# final.net
KiCad netlist of a schematic drawn in EAGLE
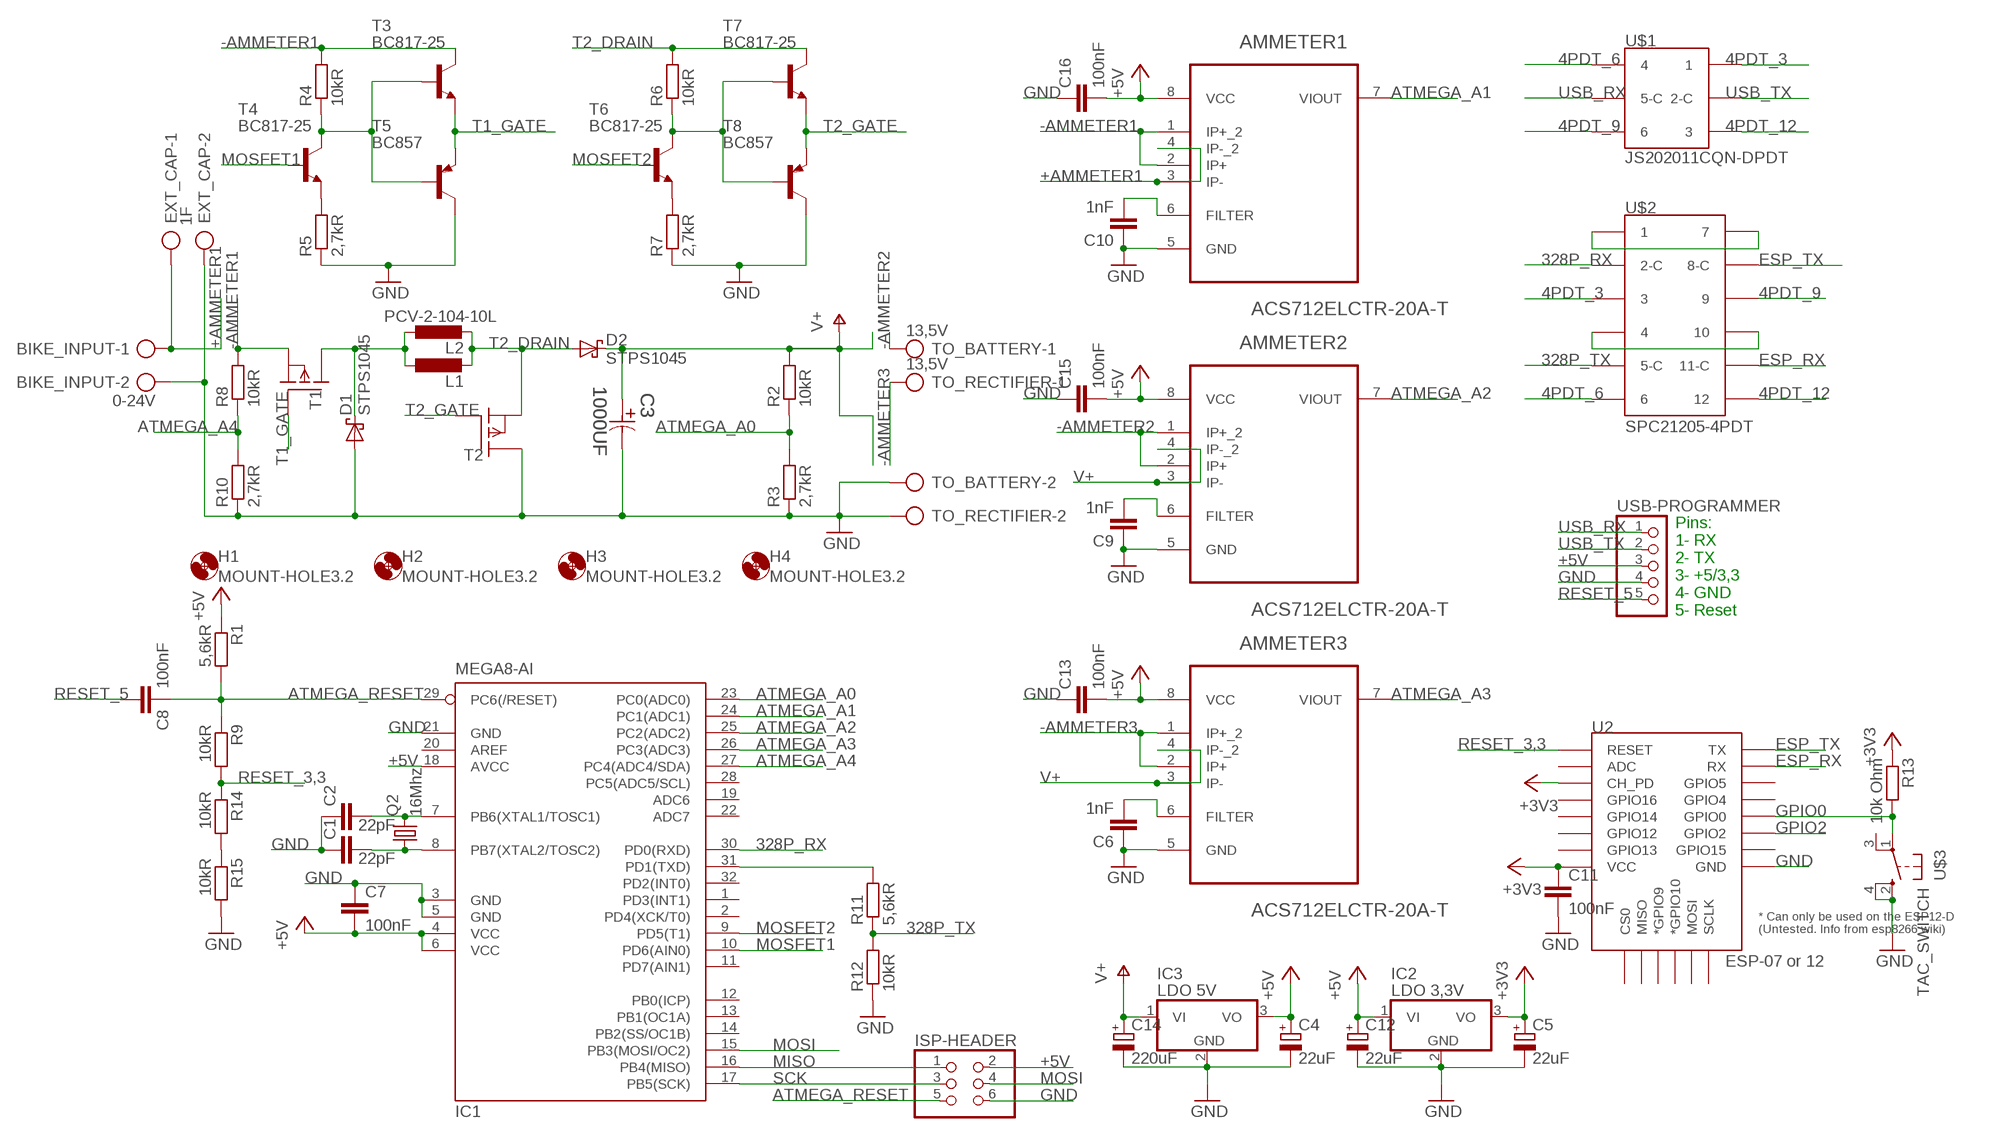
[diagram p0: schematic, sheet 1]

(export (version "E")
  (design (tool "Eeschema 10.0.6"))
  (components
    (comp (ref "AMMETER1")
      (value "ACS712ELCTR-20A-T")
      (footprint "eagle-import:SOIC127P600X175-8N")
      (libsource (lib "eagle-import") (part "ACS712ELCTR-20A-T"))
    )
    (comp (ref "AMMETER2")
      (value "ACS712ELCTR-20A-T")
      (footprint "eagle-import:SOIC127P600X175-8N")
      (libsource (lib "eagle-import") (part "ACS712ELCTR-20A-T"))
    )
    (comp (ref "AMMETER3")
      (value "ACS712ELCTR-20A-T")
      (footprint "eagle-import:SOIC127P600X175-8N")
      (libsource (lib "eagle-import") (part "ACS712ELCTR-20A-T"))
    )
    (comp (ref "BIKE_INPUT")
      (value "0-24V")
      (footprint "eagle-import:AK500_2")
      (libsource (lib "eagle-import") (part "AK500/2"))
    )
    (comp (ref "C1")
      (value "22pF")
      (footprint "eagle-import:C0805")
      (libsource (lib "eagle-import") (part "C-EUC0805"))
    )
    (comp (ref "C2")
      (value "22pF")
      (footprint "eagle-import:C0805")
      (libsource (lib "eagle-import") (part "C-EUC0805"))
    )
    (comp (ref "C3")
      (value "1000UF")
      (footprint "eagle-import:CAPAE1700X1700N")
      (fields (field (name "MPN") "EEVFK1H102M") (field (name "TOLERANCE") "±20 %"))
      (libsource (lib "eagle-import") (part "EEV--CASE-J16FK1H102M"))
    )
    (comp (ref "C4")
      (value "22uF")
      (footprint "eagle-import:153CLV-0505")
      (libsource (lib "eagle-import") (part "CPOL-EU153CLV-0505"))
    )
    (comp (ref "C5")
      (value "22uF")
      (footprint "eagle-import:153CLV-0505")
      (libsource (lib "eagle-import") (part "CPOL-EU153CLV-0505"))
    )
    (comp (ref "C6")
      (value "1nF")
      (footprint "eagle-import:C0805")
      (libsource (lib "eagle-import") (part "C-EUC0805"))
    )
    (comp (ref "C7")
      (value "100nF")
      (footprint "eagle-import:C0805")
      (libsource (lib "eagle-import") (part "C-EUC0805"))
    )
    (comp (ref "C8")
      (value "100nF")
      (footprint "eagle-import:C0805")
      (libsource (lib "eagle-import") (part "C-EUC0805"))
    )
    (comp (ref "C9")
      (value "1nF")
      (footprint "eagle-import:C0805")
      (libsource (lib "eagle-import") (part "C-EUC0805"))
    )
    (comp (ref "C10")
      (value "1nF")
      (footprint "eagle-import:C0805")
      (libsource (lib "eagle-import") (part "C-EUC0805"))
    )
    (comp (ref "C11")
      (value "100nF")
      (footprint "eagle-import:C0805")
      (libsource (lib "eagle-import") (part "C-EUC0805"))
    )
    (comp (ref "C12")
      (value "22uF")
      (footprint "eagle-import:153CLV-0505")
      (libsource (lib "eagle-import") (part "CPOL-EU153CLV-0505"))
    )
    (comp (ref "C13")
      (value "100nF")
      (footprint "eagle-import:C0805")
      (libsource (lib "eagle-import") (part "C-EUC0805"))
    )
    (comp (ref "C14")
      (value "220uF")
      (footprint "eagle-import:153CLV-0807")
      (libsource (lib "eagle-import") (part "CPOL-EU153CLV-0807"))
    )
    (comp (ref "C15")
      (value "100nF")
      (footprint "eagle-import:C0805")
      (libsource (lib "eagle-import") (part "C-EUC0805"))
    )
    (comp (ref "C16")
      (value "100nF")
      (footprint "eagle-import:C0805")
      (libsource (lib "eagle-import") (part "C-EUC0805"))
    )
    (comp (ref "D1")
      (value "STPS1045")
      (footprint "eagle-import:TO220AC")
      (libsource (lib "eagle-import") (part "STPS1045"))
    )
    (comp (ref "D2")
      (value "STPS1045")
      (footprint "eagle-import:TO220AC")
      (libsource (lib "eagle-import") (part "STPS1045"))
    )
    (comp (ref "EXT_CAP")
      (value "1F")
      (footprint "eagle-import:AK500_2")
      (libsource (lib "eagle-import") (part "AK500/2"))
    )
    (comp (ref "H1")
      (value "MOUNT-HOLE3.2")
      (footprint "eagle-import:3,2")
      (libsource (lib "eagle-import") (part "MOUNT-HOLE3.2"))
    )
    (comp (ref "H2")
      (value "MOUNT-HOLE3.2")
      (footprint "eagle-import:3,2")
      (libsource (lib "eagle-import") (part "MOUNT-HOLE3.2"))
    )
    (comp (ref "H3")
      (value "MOUNT-HOLE3.2")
      (footprint "eagle-import:3,2")
      (libsource (lib "eagle-import") (part "MOUNT-HOLE3.2"))
    )
    (comp (ref "H4")
      (value "MOUNT-HOLE3.2")
      (footprint "eagle-import:3,2")
      (libsource (lib "eagle-import") (part "MOUNT-HOLE3.2"))
    )
    (comp (ref "IC1")
      (value "MEGA8-AI")
      (footprint "eagle-import:TQFP32-08")
      (fields (field (name "MPN") "ATMEGA8-16AU"))
      (libsource (lib "eagle-import") (part "MEGA8-AI"))
    )
    (comp (ref "IC2")
      (value "LDO 3,3V")
      (footprint "eagle-import:SOT223")
      (libsource (lib "eagle-import") (part "MCP1703DB"))
    )
    (comp (ref "IC3")
      (value "LDO 5V")
      (footprint "eagle-import:SOT223")
      (libsource (lib "eagle-import") (part "MCP1703DB"))
    )
    (comp (ref "ISP-HEADER")
      (value "PINHD-2X3")
      (footprint "eagle-import:2X03")
      (libsource (lib "eagle-import") (part "PINHD-2X3"))
    )
    (comp (ref "L1")
      (value "PCV-2-104-10L")
      (footprint "eagle-import:TJ5-U2")
      (libsource (lib "eagle-import") (part "PCV-2-104-10L"))
    )
    (comp (ref "L2")
      (value "PCV-2-104-10L")
      (footprint "eagle-import:TJ5-U2")
      (libsource (lib "eagle-import") (part "PCV-2-104-10L"))
    )
    (comp (ref "Q2")
      (value "16Mhz")
      (footprint "eagle-import:HC49UP")
      (libsource (lib "eagle-import") (part "CRYSTALHC49UP"))
    )
    (comp (ref "R1")
      (value "5,6kR")
      (footprint "eagle-import:M0805")
      (libsource (lib "eagle-import") (part "R-EU_M0805"))
    )
    (comp (ref "R2")
      (value "10kR")
      (footprint "eagle-import:M0805")
      (libsource (lib "eagle-import") (part "R-EU_M0805"))
    )
    (comp (ref "R3")
      (value "2,7kR")
      (footprint "eagle-import:M0805")
      (libsource (lib "eagle-import") (part "R-EU_M0805"))
    )
    (comp (ref "R4")
      (value "10kR")
      (footprint "eagle-import:M0805")
      (libsource (lib "eagle-import") (part "R-EU_M0805"))
    )
    (comp (ref "R5")
      (value "2,7kR")
      (footprint "eagle-import:M0805")
      (libsource (lib "eagle-import") (part "R-EU_M0805"))
    )
    (comp (ref "R6")
      (value "10kR")
      (footprint "eagle-import:M0805")
      (libsource (lib "eagle-import") (part "R-EU_M0805"))
    )
    (comp (ref "R7")
      (value "2,7kR")
      (footprint "eagle-import:M0805")
      (libsource (lib "eagle-import") (part "R-EU_M0805"))
    )
    (comp (ref "R8")
      (value "10kR")
      (footprint "eagle-import:M0805")
      (libsource (lib "eagle-import") (part "R-EU_M0805"))
    )
    (comp (ref "R9")
      (value "10kR")
      (footprint "eagle-import:M0805")
      (libsource (lib "eagle-import") (part "R-EU_M0805"))
    )
    (comp (ref "R10")
      (value "2,7kR")
      (footprint "eagle-import:M0805")
      (libsource (lib "eagle-import") (part "R-EU_M0805"))
    )
    (comp (ref "R11")
      (value "5,6kR")
      (footprint "eagle-import:M0805")
      (libsource (lib "eagle-import") (part "R-EU_M0805"))
    )
    (comp (ref "R12")
      (value "10kR")
      (footprint "eagle-import:M0805")
      (libsource (lib "eagle-import") (part "R-EU_M0805"))
    )
    (comp (ref "R13")
      (value "10k Ohm")
      (footprint "eagle-import:M0805")
      (libsource (lib "eagle-import") (part "R-EU_M0805"))
    )
    (comp (ref "R14")
      (value "10kR")
      (footprint "eagle-import:M0805")
      (libsource (lib "eagle-import") (part "R-EU_M0805"))
    )
    (comp (ref "R15")
      (value "10kR")
      (footprint "eagle-import:M0805")
      (libsource (lib "eagle-import") (part "R-EU_M0805"))
    )
    (comp (ref "T1")
      (value "SUP65P06-20")
      (footprint "eagle-import:TO220")
      (libsource (lib "eagle-import") (part "SUP65P06-20"))
    )
    (comp (ref "T2")
      (value "SUP65P06-20")
      (footprint "eagle-import:TO220")
      (libsource (lib "eagle-import") (part "SUP65P06-20"))
    )
    (comp (ref "T3")
      (value "BC817-25")
      (footprint "eagle-import:SOT23-BEC")
      (libsource (lib "eagle-import") (part "-NPN-SOT23-BECBC817-25"))
    )
    (comp (ref "T4")
      (value "BC817-25")
      (footprint "eagle-import:SOT23-BEC")
      (libsource (lib "eagle-import") (part "-NPN-SOT23-BECBC817-25"))
    )
    (comp (ref "T5")
      (value "BC857")
      (footprint "eagle-import:SOT23-BEC")
      (libsource (lib "eagle-import") (part "-PNP-SOT23-BECBC857ALT1"))
    )
    (comp (ref "T6")
      (value "BC817-25")
      (footprint "eagle-import:SOT23-BEC")
      (libsource (lib "eagle-import") (part "-NPN-SOT23-BECBC817-25"))
    )
    (comp (ref "T7")
      (value "BC817-25")
      (footprint "eagle-import:SOT23-BEC")
      (libsource (lib "eagle-import") (part "-NPN-SOT23-BECBC817-25"))
    )
    (comp (ref "T8")
      (value "BC857")
      (footprint "eagle-import:SOT23-BEC")
      (libsource (lib "eagle-import") (part "-PNP-SOT23-BECBC857ALT1"))
    )
    (comp (ref "TO_BATTERY")
      (value "13,5V")
      (footprint "eagle-import:AK500_2")
      (libsource (lib "eagle-import") (part "AK500/2"))
    )
    (comp (ref "TO_RECTIFIER")
      (value "13,5V")
      (footprint "eagle-import:AK500_2")
      (libsource (lib "eagle-import") (part "AK500/2"))
    )
    (comp (ref "U$1")
      (value "JS202011CQN-DPDT")
      (footprint "eagle-import:2X3_SWITCH")
      (libsource (lib "eagle-import") (part "JS202011CQN-DPDT"))
    )
    (comp (ref "U$2")
      (value "SPC21205-4PDT")
      (footprint "eagle-import:2X6_SWITCH")
      (libsource (lib "eagle-import") (part "SPC21205-4PDT"))
    )
    (comp (ref "U$3")
      (value "TAC_SWITCH")
      (footprint "eagle-import:TL1105SP")
      (libsource (lib "eagle-import") (part "TAC_SWITCH"))
    )
    (comp (ref "U2")
      (value "ESP-07 or 12")
      (footprint "eagle-import:ESP12E-SMD")
      (libsource (lib "eagle-import") (part "ESP12ESMD"))
    )
    (comp (ref "USB-PROGRAMMER")
      (value "PINHD-1X5")
      (footprint "eagle-import:1X05")
      (libsource (lib "eagle-import") (part "PINHD-1X5"))
    )
  )
  (nets
    (net (code "1") (name "+3V3") (class "Default")
      (node (ref "C11") (pin "1") (pinfunction "1_1") (pintype "passive"))
      (node (ref "C5") (pin "+") (pinfunction "+_+") (pintype "passive"))
      (node (ref "IC2") (pin "3") (pinfunction "VO_3") (pintype "passive"))
      (node (ref "R13") (pin "1") (pinfunction "1_1") (pintype "passive"))
      (node (ref "U2") (pin "CH_PD") (pinfunction "CH_PD_CH_PD") (pintype "bidirectional"))
      (node (ref "U2") (pin "VCC") (pinfunction "VCC_VCC") (pintype "bidirectional"))
    )
    (net (code "2") (name "+5V") (class "Default")
      (node (ref "AMMETER1") (pin "8") (pinfunction "VCC_8") (pintype "power_in"))
      (node (ref "AMMETER2") (pin "8") (pinfunction "VCC_8") (pintype "power_in"))
      (node (ref "AMMETER3") (pin "8") (pinfunction "VCC_8") (pintype "power_in"))
      (node (ref "C12") (pin "+") (pinfunction "+_+") (pintype "passive"))
      (node (ref "C13") (pin "2") (pinfunction "2_2") (pintype "passive"))
      (node (ref "C15") (pin "2") (pinfunction "2_2") (pintype "passive"))
      (node (ref "C16") (pin "2") (pinfunction "2_2") (pintype "passive"))
      (node (ref "C4") (pin "+") (pinfunction "+_+") (pintype "passive"))
      (node (ref "C7") (pin "2") (pinfunction "2_2") (pintype "passive"))
      (node (ref "IC1") (pin "18") (pinfunction "AVCC_18") (pintype "power_in"))
      (node (ref "IC1") (pin "4") (pinfunction "VCC_4") (pintype "power_in"))
      (node (ref "IC1") (pin "6") (pinfunction "VCC_6") (pintype "power_in"))
      (node (ref "IC2") (pin "1") (pinfunction "VI_1") (pintype "input"))
      (node (ref "IC3") (pin "3") (pinfunction "VO_3") (pintype "passive"))
      (node (ref "ISP-HEADER") (pin "2") (pinfunction "2_2") (pintype "passive"))
      (node (ref "R1") (pin "1") (pinfunction "1_1") (pintype "passive"))
      (node (ref "USB-PROGRAMMER") (pin "3") (pinfunction "3_3") (pintype "passive"))
    )
    (net (code "3") (name "/+AMMETER1") (class "Default")
      (node (ref "AMMETER1") (pin "3") (pinfunction "IP-_3") (pintype "input"))
      (node (ref "AMMETER1") (pin "4") (pinfunction "IP-_2_4") (pintype "input"))
      (node (ref "BIKE_INPUT") (pin "1") (pinfunction "KL_1") (pintype "passive"))
      (node (ref "EXT_CAP") (pin "1") (pinfunction "KL_1") (pintype "passive"))
    )
    (net (code "4") (name "/-AMMETER1") (class "Default")
      (node (ref "AMMETER1") (pin "1") (pinfunction "IP+_2_1") (pintype "input"))
      (node (ref "AMMETER1") (pin "2") (pinfunction "IP+_2") (pintype "input"))
      (node (ref "R4") (pin "2") (pinfunction "2_2") (pintype "passive"))
      (node (ref "R8") (pin "2") (pinfunction "2_2") (pintype "passive"))
      (node (ref "T1") (pin "3") (pinfunction "S_3") (pintype "passive"))
      (node (ref "T3") (pin "C") (pinfunction "C_C") (pintype "passive"))
    )
    (net (code "5") (name "/-AMMETER2") (class "Default")
      (node (ref "AMMETER2") (pin "1") (pinfunction "IP+_2_1") (pintype "input"))
      (node (ref "AMMETER2") (pin "2") (pinfunction "IP+_2") (pintype "input"))
      (node (ref "TO_BATTERY") (pin "1") (pinfunction "KL_1") (pintype "passive"))
    )
    (net (code "6") (name "/-AMMETER3") (class "Default")
      (node (ref "AMMETER3") (pin "1") (pinfunction "IP+_2_1") (pintype "input"))
      (node (ref "AMMETER3") (pin "2") (pinfunction "IP+_2") (pintype "input"))
      (node (ref "TO_RECTIFIER") (pin "1") (pinfunction "KL_1") (pintype "passive"))
    )
    (net (code "7") (name "/4PDT_3") (class "Default")
      (node (ref "U$1") (pin "1") (pinfunction "1_1") (pintype "bidirectional"))
      (node (ref "U$2") (pin "3") (pinfunction "3_3") (pintype "bidirectional"))
    )
    (net (code "8") (name "/4PDT_6") (class "Default")
      (node (ref "U$1") (pin "4") (pinfunction "4_4") (pintype "bidirectional"))
      (node (ref "U$2") (pin "6") (pinfunction "6_6") (pintype "bidirectional"))
    )
    (net (code "9") (name "/4PDT_9") (class "Default")
      (node (ref "U$1") (pin "6") (pinfunction "6_6") (pintype "bidirectional"))
      (node (ref "U$2") (pin "9") (pinfunction "9_9") (pintype "bidirectional"))
    )
    (net (code "10") (name "/4PDT_12") (class "Default")
      (node (ref "U$1") (pin "3") (pinfunction "3_3") (pintype "bidirectional"))
      (node (ref "U$2") (pin "12") (pinfunction "12_12") (pintype "bidirectional"))
    )
    (net (code "11") (name "/328P_RX") (class "Default")
      (node (ref "IC1") (pin "30") (pinfunction "PD0(RXD)_30") (pintype "bidirectional"))
      (node (ref "U$2") (pin "2-C") (pinfunction "2-C_2-C") (pintype "bidirectional"))
    )
    (net (code "12") (name "/328P_TX") (class "Default")
      (node (ref "R11") (pin "1") (pinfunction "1_1") (pintype "passive"))
      (node (ref "R12") (pin "2") (pinfunction "2_2") (pintype "passive"))
      (node (ref "U$2") (pin "5-C") (pinfunction "5-C_5-C") (pintype "bidirectional"))
    )
    (net (code "13") (name "/ATMEGA_A0") (class "Default")
      (node (ref "IC1") (pin "23") (pinfunction "PC0(ADC0)_23") (pintype "bidirectional"))
      (node (ref "R2") (pin "1") (pinfunction "1_1") (pintype "passive"))
      (node (ref "R3") (pin "2") (pinfunction "2_2") (pintype "passive"))
    )
    (net (code "14") (name "/ATMEGA_A1") (class "Default")
      (node (ref "AMMETER1") (pin "7") (pinfunction "VIOUT_7") (pintype "output"))
      (node (ref "IC1") (pin "24") (pinfunction "PC1(ADC1)_24") (pintype "bidirectional"))
    )
    (net (code "15") (name "/ATMEGA_A2") (class "Default")
      (node (ref "AMMETER2") (pin "7") (pinfunction "VIOUT_7") (pintype "output"))
      (node (ref "IC1") (pin "25") (pinfunction "PC2(ADC2)_25") (pintype "bidirectional"))
    )
    (net (code "16") (name "/ATMEGA_A3") (class "Default")
      (node (ref "AMMETER3") (pin "7") (pinfunction "VIOUT_7") (pintype "output"))
      (node (ref "IC1") (pin "26") (pinfunction "PC3(ADC3)_26") (pintype "bidirectional"))
    )
    (net (code "17") (name "/ATMEGA_A4") (class "Default")
      (node (ref "IC1") (pin "27") (pinfunction "PC4(ADC4/SDA)_27") (pintype "bidirectional"))
      (node (ref "R10") (pin "2") (pinfunction "2_2") (pintype "passive"))
      (node (ref "R8") (pin "1") (pinfunction "1_1") (pintype "passive"))
    )
    (net (code "18") (name "/ATMEGA_RESET") (class "Default")
      (node (ref "C8") (pin "1") (pinfunction "1_1") (pintype "passive"))
      (node (ref "IC1") (pin "29") (pinfunction "PC6(/RESET)_29") (pintype "bidirectional"))
      (node (ref "ISP-HEADER") (pin "5") (pinfunction "5_5") (pintype "passive"))
      (node (ref "R1") (pin "2") (pinfunction "2_2") (pintype "passive"))
      (node (ref "R9") (pin "1") (pinfunction "1_1") (pintype "passive"))
    )
    (net (code "19") (name "/ESP_RX") (class "Default")
      (node (ref "U$2") (pin "11-C") (pinfunction "11-C_11-C") (pintype "bidirectional"))
      (node (ref "U2") (pin "RXD0") (pinfunction "RX_RXD0") (pintype "bidirectional"))
    )
    (net (code "20") (name "/ESP_TX") (class "Default")
      (node (ref "U$2") (pin "8-C") (pinfunction "8-C_8-C") (pintype "bidirectional"))
      (node (ref "U2") (pin "TXD0") (pinfunction "TX_TXD0") (pintype "bidirectional"))
    )
    (net (code "21") (name "/GPIO0") (class "Default")
      (node (ref "R13") (pin "2") (pinfunction "2_2") (pintype "passive"))
      (node (ref "U$3") (pin "1") (pinfunction "P_1") (pintype "passive"))
      (node (ref "U2") (pin "GPIO0") (pinfunction "GPIO0_GPIO0") (pintype "bidirectional"))
    )
    (net (code "22") (name "/GPIO2") (class "Default")
      (node (ref "U2") (pin "GPIO2") (pinfunction "GPIO2_GPIO2") (pintype "bidirectional"))
    )
    (net (code "23") (name "/MISO") (class "Default")
      (node (ref "IC1") (pin "16") (pinfunction "PB4(MISO)_16") (pintype "bidirectional"))
      (node (ref "ISP-HEADER") (pin "1") (pinfunction "1_1") (pintype "passive"))
    )
    (net (code "24") (name "/MOSFET1") (class "Default")
      (node (ref "IC1") (pin "10") (pinfunction "PD6(AIN0)_10") (pintype "bidirectional"))
      (node (ref "T4") (pin "B") (pinfunction "B_B") (pintype "passive"))
    )
    (net (code "25") (name "/MOSFET2") (class "Default")
      (node (ref "IC1") (pin "9") (pinfunction "PD5(T1)_9") (pintype "bidirectional"))
      (node (ref "T6") (pin "B") (pinfunction "B_B") (pintype "passive"))
    )
    (net (code "26") (name "/MOSI") (class "Default")
      (node (ref "IC1") (pin "15") (pinfunction "PB3(MOSI/OC2)_15") (pintype "bidirectional"))
      (node (ref "ISP-HEADER") (pin "4") (pinfunction "4_4") (pintype "passive"))
    )
    (net (code "27") (name "/RESET_3,3") (class "Default")
      (node (ref "R14") (pin "1") (pinfunction "1_1") (pintype "passive"))
      (node (ref "R9") (pin "2") (pinfunction "2_2") (pintype "passive"))
      (node (ref "U2") (pin "RESET") (pinfunction "RESET_RESET") (pintype "bidirectional"))
    )
    (net (code "28") (name "/RESET_5") (class "Default")
      (node (ref "C8") (pin "2") (pinfunction "2_2") (pintype "passive"))
      (node (ref "USB-PROGRAMMER") (pin "5") (pinfunction "5_5") (pintype "passive"))
    )
    (net (code "29") (name "/SCK") (class "Default")
      (node (ref "IC1") (pin "17") (pinfunction "PB5(SCK)_17") (pintype "bidirectional"))
      (node (ref "ISP-HEADER") (pin "3") (pinfunction "3_3") (pintype "passive"))
    )
    (net (code "30") (name "/T1_GATE") (class "Default")
      (node (ref "T1") (pin "1") (pinfunction "G_1") (pintype "passive"))
      (node (ref "T3") (pin "E") (pinfunction "E_E") (pintype "passive"))
      (node (ref "T5") (pin "E") (pinfunction "E_E") (pintype "passive"))
    )
    (net (code "31") (name "/T2_DRAIN") (class "Default")
      (node (ref "D2") (pin "A") (pinfunction "A_A") (pintype "passive"))
      (node (ref "L1") (pin "2") (pinfunction "2_2") (pintype "passive"))
      (node (ref "L2") (pin "2") (pinfunction "2_2") (pintype "passive"))
      (node (ref "R6") (pin "2") (pinfunction "2_2") (pintype "passive"))
      (node (ref "T2") (pin "3") (pinfunction "S_3") (pintype "passive"))
      (node (ref "T7") (pin "C") (pinfunction "C_C") (pintype "passive"))
    )
    (net (code "32") (name "/T2_GATE") (class "Default")
      (node (ref "T2") (pin "1") (pinfunction "G_1") (pintype "passive"))
      (node (ref "T7") (pin "E") (pinfunction "E_E") (pintype "passive"))
      (node (ref "T8") (pin "E") (pinfunction "E_E") (pintype "passive"))
    )
    (net (code "33") (name "/USB_RX") (class "Default")
      (node (ref "U$1") (pin "5-C") (pinfunction "5-C_5-C") (pintype "bidirectional"))
      (node (ref "USB-PROGRAMMER") (pin "1") (pinfunction "1_1") (pintype "passive"))
    )
    (net (code "34") (name "/USB_TX") (class "Default")
      (node (ref "U$1") (pin "2-C") (pinfunction "2-C_2-C") (pintype "bidirectional"))
      (node (ref "USB-PROGRAMMER") (pin "2") (pinfunction "2_2") (pintype "passive"))
    )
    (net (code "35") (name "GND") (class "Default")
      (node (ref "AMMETER1") (pin "5") (pinfunction "GND_5") (pintype "passive"))
      (node (ref "AMMETER2") (pin "5") (pinfunction "GND_5") (pintype "passive"))
      (node (ref "AMMETER3") (pin "5") (pinfunction "GND_5") (pintype "passive"))
      (node (ref "BIKE_INPUT") (pin "2") (pinfunction "KL_2") (pintype "passive"))
      (node (ref "C1") (pin "1") (pinfunction "1_1") (pintype "passive"))
      (node (ref "C10") (pin "1") (pinfunction "1_1") (pintype "passive"))
      (node (ref "C11") (pin "2") (pinfunction "2_2") (pintype "passive"))
      (node (ref "C12") (pin "-") (pinfunction "-_-") (pintype "passive"))
      (node (ref "C13") (pin "1") (pinfunction "1_1") (pintype "passive"))
      (node (ref "C14") (pin "-") (pinfunction "-_-") (pintype "passive"))
      (node (ref "C15") (pin "1") (pinfunction "1_1") (pintype "passive"))
      (node (ref "C16") (pin "1") (pinfunction "1_1") (pintype "passive"))
      (node (ref "C2") (pin "1") (pinfunction "1_1") (pintype "passive"))
      (node (ref "C3") (pin "2") (pinfunction "2_2") (pintype "passive"))
      (node (ref "C4") (pin "-") (pinfunction "-_-") (pintype "passive"))
      (node (ref "C5") (pin "-") (pinfunction "-_-") (pintype "passive"))
      (node (ref "C6") (pin "1") (pinfunction "1_1") (pintype "passive"))
      (node (ref "C7") (pin "1") (pinfunction "1_1") (pintype "passive"))
      (node (ref "C9") (pin "1") (pinfunction "1_1") (pintype "passive"))
      (node (ref "D1") (pin "A") (pinfunction "A_A") (pintype "passive"))
      (node (ref "EXT_CAP") (pin "2") (pinfunction "KL_2") (pintype "passive"))
      (node (ref "IC1") (pin "21") (pinfunction "GND_21") (pintype "power_in"))
      (node (ref "IC1") (pin "3") (pinfunction "GND_3") (pintype "power_in"))
      (node (ref "IC1") (pin "5") (pinfunction "GND_5") (pintype "power_in"))
      (node (ref "IC2") (pin "2") (pinfunction "GND_2") (pintype "passive"))
      (node (ref "IC3") (pin "2") (pinfunction "GND_2") (pintype "passive"))
      (node (ref "ISP-HEADER") (pin "6") (pinfunction "6_6") (pintype "passive"))
      (node (ref "R10") (pin "1") (pinfunction "1_1") (pintype "passive"))
      (node (ref "R12") (pin "1") (pinfunction "1_1") (pintype "passive"))
      (node (ref "R15") (pin "2") (pinfunction "2_2") (pintype "passive"))
      (node (ref "R3") (pin "1") (pinfunction "1_1") (pintype "passive"))
      (node (ref "R5") (pin "1") (pinfunction "1_1") (pintype "passive"))
      (node (ref "R7") (pin "1") (pinfunction "1_1") (pintype "passive"))
      (node (ref "T2") (pin "2") (pinfunction "D_2") (pintype "passive"))
      (node (ref "T5") (pin "C") (pinfunction "C_C") (pintype "passive"))
      (node (ref "T8") (pin "C") (pinfunction "C_C") (pintype "passive"))
      (node (ref "TO_BATTERY") (pin "2") (pinfunction "KL_2") (pintype "passive"))
      (node (ref "TO_RECTIFIER") (pin "2") (pinfunction "KL_2") (pintype "passive"))
      (node (ref "U$3") (pin "2") (pinfunction "S_2") (pintype "passive"))
      (node (ref "U$3") (pin "4") (pinfunction "S1_4") (pintype "passive"))
      (node (ref "U2") (pin "GND") (pinfunction "GND_GND") (pintype "bidirectional"))
      (node (ref "USB-PROGRAMMER") (pin "4") (pinfunction "4_4") (pintype "passive"))
    )
    (net (code "36") (name "Net-(AMMETER1-FILTER)") (class "Default")
      (node (ref "AMMETER1") (pin "6") (pinfunction "FILTER_6") (pintype "input"))
      (node (ref "C10") (pin "2") (pinfunction "2_2") (pintype "passive"))
    )
    (net (code "37") (name "Net-(AMMETER2-FILTER)") (class "Default")
      (node (ref "AMMETER2") (pin "6") (pinfunction "FILTER_6") (pintype "input"))
      (node (ref "C9") (pin "2") (pinfunction "2_2") (pintype "passive"))
    )
    (net (code "38") (name "Net-(AMMETER3-FILTER)") (class "Default")
      (node (ref "AMMETER3") (pin "6") (pinfunction "FILTER_6") (pintype "input"))
      (node (ref "C6") (pin "2") (pinfunction "2_2") (pintype "passive"))
    )
    (net (code "39") (name "Net-(IC1-PB6(XTAL1{slash}TOSC1))") (class "Default")
      (node (ref "C2") (pin "2") (pinfunction "2_2") (pintype "passive"))
      (node (ref "IC1") (pin "7") (pinfunction "PB6(XTAL1/TOSC1)_7") (pintype "bidirectional"))
      (node (ref "Q2") (pin "2") (pinfunction "2_2") (pintype "passive"))
    )
    (net (code "40") (name "Net-(IC1-PB7(XTAL2{slash}TOSC2))") (class "Default")
      (node (ref "C1") (pin "2") (pinfunction "2_2") (pintype "passive"))
      (node (ref "IC1") (pin "8") (pinfunction "PB7(XTAL2/TOSC2)_8") (pintype "bidirectional"))
      (node (ref "Q2") (pin "1") (pinfunction "1_1") (pintype "passive"))
    )
    (net (code "41") (name "Net-(IC1-PD1(TXD))") (class "Default")
      (node (ref "IC1") (pin "31") (pinfunction "PD1(TXD)_31") (pintype "bidirectional"))
      (node (ref "R11") (pin "2") (pinfunction "2_2") (pintype "passive"))
    )
    (net (code "42") (name "Net-(R4-Pad1)") (class "Default")
      (node (ref "R4") (pin "1") (pinfunction "1_1") (pintype "passive"))
      (node (ref "T3") (pin "B") (pinfunction "B_B") (pintype "passive"))
      (node (ref "T4") (pin "C") (pinfunction "C_C") (pintype "passive"))
      (node (ref "T5") (pin "B") (pinfunction "B_B") (pintype "passive"))
    )
    (net (code "43") (name "Net-(R5-Pad2)") (class "Default")
      (node (ref "R5") (pin "2") (pinfunction "2_2") (pintype "passive"))
      (node (ref "T4") (pin "E") (pinfunction "E_E") (pintype "passive"))
    )
    (net (code "44") (name "Net-(R6-Pad1)") (class "Default")
      (node (ref "R6") (pin "1") (pinfunction "1_1") (pintype "passive"))
      (node (ref "T6") (pin "C") (pinfunction "C_C") (pintype "passive"))
      (node (ref "T7") (pin "B") (pinfunction "B_B") (pintype "passive"))
      (node (ref "T8") (pin "B") (pinfunction "B_B") (pintype "passive"))
    )
    (net (code "45") (name "Net-(R7-Pad2)") (class "Default")
      (node (ref "R7") (pin "2") (pinfunction "2_2") (pintype "passive"))
      (node (ref "T6") (pin "E") (pinfunction "E_E") (pintype "passive"))
    )
    (net (code "46") (name "Net-(R14-Pad2)") (class "Default")
      (node (ref "R14") (pin "2") (pinfunction "2_2") (pintype "passive"))
      (node (ref "R15") (pin "1") (pinfunction "1_1") (pintype "passive"))
    )
    (net (code "47") (name "Net-(T1-D)") (class "Default")
      (node (ref "D1") (pin "C") (pinfunction "C_C") (pintype "passive"))
      (node (ref "L1") (pin "1") (pinfunction "1_1") (pintype "passive"))
      (node (ref "L2") (pin "1") (pinfunction "1_1") (pintype "passive"))
      (node (ref "T1") (pin "2") (pinfunction "D_2") (pintype "passive"))
    )
    (net (code "48") (name "Net-(U$2-Pad1)") (class "Default")
      (node (ref "U$2") (pin "1") (pinfunction "1_1") (pintype "bidirectional"))
      (node (ref "U$2") (pin "7") (pinfunction "7_7") (pintype "bidirectional"))
    )
    (net (code "49") (name "Net-(U$2-Pad10)") (class "Default")
      (node (ref "U$2") (pin "10") (pinfunction "10_10") (pintype "bidirectional"))
      (node (ref "U$2") (pin "4") (pinfunction "4_4") (pintype "bidirectional"))
    )
    (net (code "50") (name "V+") (class "Default")
      (node (ref "AMMETER2") (pin "3") (pinfunction "IP-_3") (pintype "input"))
      (node (ref "AMMETER2") (pin "4") (pinfunction "IP-_2_4") (pintype "input"))
      (node (ref "AMMETER3") (pin "3") (pinfunction "IP-_3") (pintype "input"))
      (node (ref "AMMETER3") (pin "4") (pinfunction "IP-_2_4") (pintype "input"))
      (node (ref "C14") (pin "+") (pinfunction "+_+") (pintype "passive"))
      (node (ref "C3") (pin "1") (pinfunction "1_1") (pintype "passive"))
      (node (ref "D2") (pin "C") (pinfunction "C_C") (pintype "passive"))
      (node (ref "IC3") (pin "1") (pinfunction "VI_1") (pintype "input"))
      (node (ref "R2") (pin "2") (pinfunction "2_2") (pintype "passive"))
    )
    (net (code "51") (name "unconnected-(IC1-ADC6-Pad19)") (class "Default")
      (node (ref "IC1") (pin "19") (pinfunction "ADC6_19") (pintype "bidirectional"))
    )
    (net (code "52") (name "unconnected-(IC1-ADC7-Pad22)") (class "Default")
      (node (ref "IC1") (pin "22") (pinfunction "ADC7_22") (pintype "bidirectional"))
    )
    (net (code "53") (name "unconnected-(IC1-AREF-Pad20)") (class "Default")
      (node (ref "IC1") (pin "20") (pinfunction "AREF_20") (pintype "passive"))
    )
    (net (code "54") (name "unconnected-(IC1-PB0(ICP)-Pad12)") (class "Default")
      (node (ref "IC1") (pin "12") (pinfunction "PB0(ICP)_12") (pintype "bidirectional"))
    )
    (net (code "55") (name "unconnected-(IC1-PB1(OC1A)-Pad13)") (class "Default")
      (node (ref "IC1") (pin "13") (pinfunction "PB1(OC1A)_13") (pintype "bidirectional"))
    )
    (net (code "56") (name "unconnected-(IC1-PB2(SS{slash}OC1B)-Pad14)") (class "Default")
      (node (ref "IC1") (pin "14") (pinfunction "PB2(SS/OC1B)_14") (pintype "bidirectional"))
    )
    (net (code "57") (name "unconnected-(IC1-PC5(ADC5{slash}SCL)-Pad28)") (class "Default")
      (node (ref "IC1") (pin "28") (pinfunction "PC5(ADC5/SCL)_28") (pintype "bidirectional"))
    )
    (net (code "58") (name "unconnected-(IC1-PD2(INT0)-Pad32)") (class "Default")
      (node (ref "IC1") (pin "32") (pinfunction "PD2(INT0)_32") (pintype "bidirectional"))
    )
    (net (code "59") (name "unconnected-(IC1-PD3(INT1)-Pad1)") (class "Default")
      (node (ref "IC1") (pin "1") (pinfunction "PD3(INT1)_1") (pintype "bidirectional"))
    )
    (net (code "60") (name "unconnected-(IC1-PD4(XCK{slash}T0)-Pad2)") (class "Default")
      (node (ref "IC1") (pin "2") (pinfunction "PD4(XCK/T0)_2") (pintype "bidirectional"))
    )
    (net (code "61") (name "unconnected-(IC1-PD7(AIN1)-Pad11)") (class "Default")
      (node (ref "IC1") (pin "11") (pinfunction "PD7(AIN1)_11") (pintype "bidirectional"))
    )
    (net (code "62") (name "unconnected-(U$3-P1-Pad3)") (class "Default")
      (node (ref "U$3") (pin "3") (pinfunction "P1_3") (pintype "passive"))
    )
    (net (code "63") (name "unconnected-(U2-*GPIO9-PadGPIO9)") (class "Default")
      (node (ref "U2") (pin "GPIO9") (pinfunction "*GPIO9_GPIO9") (pintype "bidirectional"))
    )
    (net (code "64") (name "unconnected-(U2-*GPIO10-PadGPIO10)") (class "Default")
      (node (ref "U2") (pin "GPIO10") (pinfunction "*GPIO10_GPIO10") (pintype "bidirectional"))
    )
    (net (code "65") (name "unconnected-(U2-PadADC)") (class "Default")
      (node (ref "U2") (pin "ADC") (pinfunction "ADC_ADC") (pintype "bidirectional"))
    )
    (net (code "66") (name "unconnected-(U2-PadCS0)") (class "Default")
      (node (ref "U2") (pin "CS0") (pinfunction "CS0_CS0") (pintype "bidirectional"))
    )
    (net (code "67") (name "unconnected-(U2-PadGPIO4)") (class "Default")
      (node (ref "U2") (pin "GPIO4") (pinfunction "GPIO4_GPIO4") (pintype "bidirectional"))
    )
    (net (code "68") (name "unconnected-(U2-PadGPIO5)") (class "Default")
      (node (ref "U2") (pin "GPIO5") (pinfunction "GPIO5_GPIO5") (pintype "bidirectional"))
    )
    (net (code "69") (name "unconnected-(U2-PadGPIO12)") (class "Default")
      (node (ref "U2") (pin "GPIO12") (pinfunction "GPIO12_GPIO12") (pintype "bidirectional"))
    )
    (net (code "70") (name "unconnected-(U2-PadGPIO13)") (class "Default")
      (node (ref "U2") (pin "GPIO13") (pinfunction "GPIO13_GPIO13") (pintype "bidirectional"))
    )
    (net (code "71") (name "unconnected-(U2-PadGPIO14)") (class "Default")
      (node (ref "U2") (pin "GPIO14") (pinfunction "GPIO14_GPIO14") (pintype "bidirectional"))
    )
    (net (code "72") (name "unconnected-(U2-PadGPIO15)") (class "Default")
      (node (ref "U2") (pin "GPIO15") (pinfunction "GPIO15_GPIO15") (pintype "bidirectional"))
    )
    (net (code "73") (name "unconnected-(U2-PadGPIO16)") (class "Default")
      (node (ref "U2") (pin "GPIO16") (pinfunction "GPIO16_GPIO16") (pintype "bidirectional"))
    )
    (net (code "74") (name "unconnected-(U2-PadMISO)") (class "Default")
      (node (ref "U2") (pin "MISO") (pinfunction "MISO_MISO") (pintype "bidirectional"))
    )
    (net (code "75") (name "unconnected-(U2-PadMOSI)") (class "Default")
      (node (ref "U2") (pin "MOSI") (pinfunction "MOSI_MOSI") (pintype "bidirectional"))
    )
    (net (code "76") (name "unconnected-(U2-PadSCLK)") (class "Default")
      (node (ref "U2") (pin "SCLK") (pinfunction "SCLK_SCLK") (pintype "bidirectional"))
    )
  )
)
